# ecu1.net
KiCad netlist of a schematic drawn in EAGLE
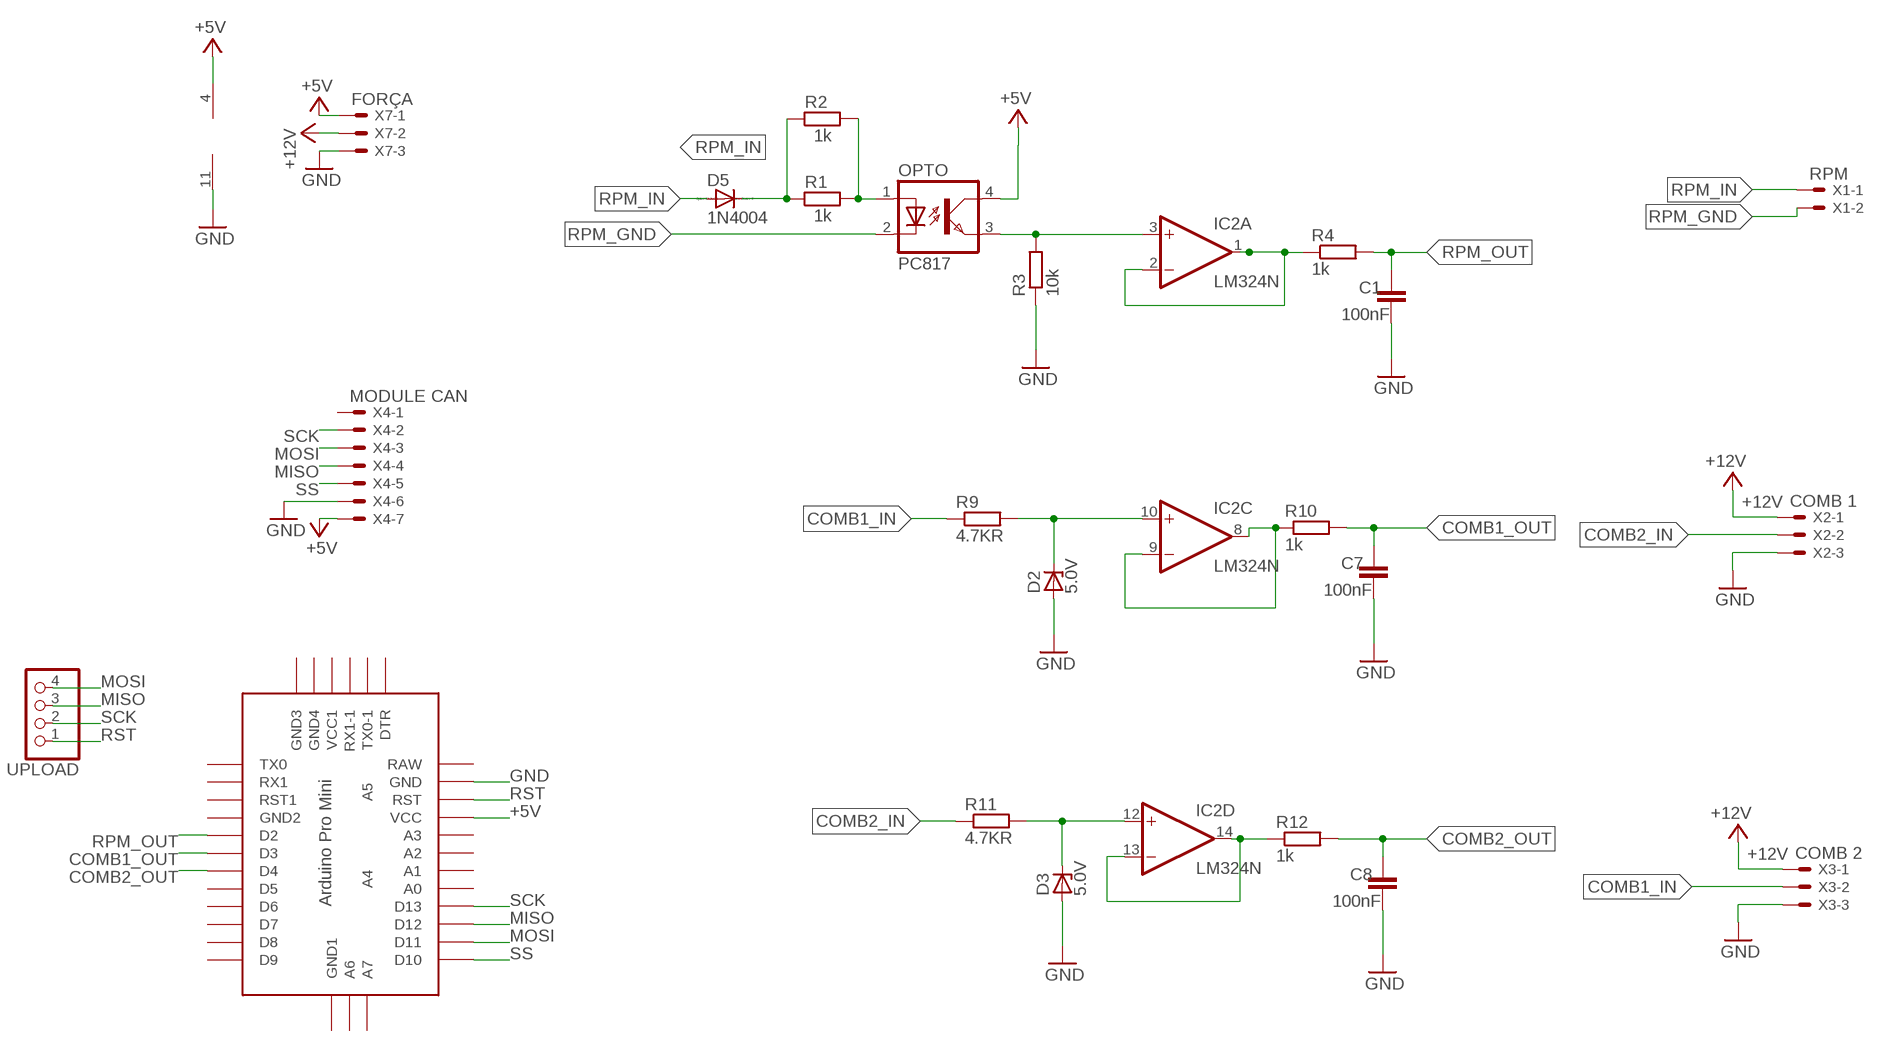
[diagram p0: schematic, sheet 1]

(export (version "E")
  (design (tool "Eeschema 10.0.6"))
  (components
    (comp (ref "C1")
      (value "100nF")
      (footprint "eagle-import:C5B2.5")
      (libsource (lib "eagle-import") (part "C5/2.5"))
    )
    (comp (ref "C7")
      (value "100nF")
      (footprint "eagle-import:C5B2.5")
      (libsource (lib "eagle-import") (part "C5/2.5"))
    )
    (comp (ref "C8")
      (value "100nF")
      (footprint "eagle-import:C5B2.5")
      (libsource (lib "eagle-import") (part "C5/2.5"))
    )
    (comp (ref "D2")
      (value "5.0V")
      (footprint "eagle-import:DO34Z7")
      (libsource (lib "eagle-import") (part "ZENER-DIODEDO34-7"))
    )
    (comp (ref "D3")
      (value "5.0V")
      (footprint "eagle-import:DO34Z7")
      (libsource (lib "eagle-import") (part "ZENER-DIODEDO34-7"))
    )
    (comp (ref "D5")
      (value "1N4004")
      (footprint "eagle-import:DO41-10")
      (libsource (lib "eagle-import") (part "1N4004"))
    )
    (comp (ref "IC2")
      (value "LM324N")
      (footprint "eagle-import:DIL14")
      (libsource (lib "eagle-import") (part "LM324N"))
    )
    (comp (ref "OPTO")
      (value "PC817")
      (footprint "eagle-import:DIL04")
      (fields (field (name "MPN") "PC817X4J000F"))
      (libsource (lib "eagle-import") (part "PC817"))
    )
    (comp (ref "R1")
      (value "1k")
      (footprint "eagle-import:0207_7")
      (libsource (lib "eagle-import") (part "R-EU_0207/7"))
    )
    (comp (ref "R2")
      (value "1k")
      (footprint "eagle-import:0207_7")
      (libsource (lib "eagle-import") (part "R-EU_0207/7"))
    )
    (comp (ref "R3")
      (value "10k")
      (footprint "eagle-import:0207_7")
      (libsource (lib "eagle-import") (part "R-EU_0207/7"))
    )
    (comp (ref "R4")
      (value "1k")
      (footprint "eagle-import:0207_7")
      (libsource (lib "eagle-import") (part "R-EU_0207/7"))
    )
    (comp (ref "R9")
      (value "4.7KR")
      (footprint "eagle-import:0207_7")
      (libsource (lib "eagle-import") (part "R-EU_0207/7"))
    )
    (comp (ref "R10")
      (value "1k")
      (footprint "eagle-import:0207_7")
      (libsource (lib "eagle-import") (part "R-EU_0207/7"))
    )
    (comp (ref "R11")
      (value "4.7KR")
      (footprint "eagle-import:0207_7")
      (libsource (lib "eagle-import") (part "R-EU_0207/7"))
    )
    (comp (ref "R12")
      (value "1k")
      (footprint "eagle-import:0207_7")
      (libsource (lib "eagle-import") (part "R-EU_0207/7"))
    )
    (comp (ref "U$1")
      (value "ABK-PRO-MINI")
      (footprint "eagle-import:ABK-PRO-MINI")
      (libsource (lib "eagle-import") (part "ABK-PRO-MINI"))
    )
    (comp (ref "UPLOAD")
      (value "PINHD-1X4")
      (footprint "eagle-import:1X04")
      (libsource (lib "eagle-import") (part "PINHD-1X4"))
    )
    (comp (ref "X1")
      (value "RPM")
      (footprint "eagle-import:22-23-2021")
      (fields (field (name "MF") "MOLEX") (field (name "MPN") "22-23-2021"))
      (libsource (lib "eagle-import") (part "22-23-2021"))
    )
    (comp (ref "X2")
      (value "COMB 1")
      (footprint "eagle-import:22-23-2031")
      (fields (field (name "MF") "MOLEX") (field (name "MPN") "22-23-2031"))
      (libsource (lib "eagle-import") (part "22-23-2031"))
    )
    (comp (ref "X3")
      (value "COMB 2")
      (footprint "eagle-import:22-23-2031")
      (fields (field (name "MF") "MOLEX") (field (name "MPN") "22-23-2031"))
      (libsource (lib "eagle-import") (part "22-23-2031"))
    )
    (comp (ref "X4")
      (value "MODULE CAN")
      (footprint "eagle-import:22-23-2071")
      (fields (field (name "MF") "MOLEX") (field (name "MPN") "22-23-2071"))
      (libsource (lib "eagle-import") (part "22-23-2071"))
    )
    (comp (ref "X7")
      (value "FORÇA")
      (footprint "eagle-import:22-23-2031")
      (fields (field (name "MF") "MOLEX") (field (name "MPN") "22-23-2031"))
      (libsource (lib "eagle-import") (part "22-23-2031"))
    )
  )
  (nets
    (net (code "1") (name "+5V") (class "Default")
      (node (ref "IC2") (pin "4") (pinfunction "V+_4") (pintype "power_in"))
      (node (ref "OPTO") (pin "4") (pinfunction "COL_4") (pintype "passive"))
      (node (ref "U$1") (pin "VCC") (pinfunction "VCC_VCC") (pintype "bidirectional"))
      (node (ref "X4") (pin "7") (pinfunction "S_7") (pintype "passive"))
      (node (ref "X7") (pin "1") (pinfunction "S_1") (pintype "passive"))
    )
    (net (code "2") (name "+12V") (class "Default")
      (node (ref "X2") (pin "1") (pinfunction "S_1") (pintype "passive"))
      (node (ref "X3") (pin "1") (pinfunction "S_1") (pintype "passive"))
      (node (ref "X7") (pin "2") (pinfunction "S_2") (pintype "passive"))
    )
    (net (code "3") (name "/MISO") (class "Default")
      (node (ref "U$1") (pin "D12") (pinfunction "D12_D12") (pintype "bidirectional"))
      (node (ref "UPLOAD") (pin "3") (pinfunction "3_3") (pintype "passive"))
      (node (ref "X4") (pin "4") (pinfunction "S_4") (pintype "passive"))
    )
    (net (code "4") (name "/MOSI") (class "Default")
      (node (ref "U$1") (pin "D11") (pinfunction "D11_D11") (pintype "bidirectional"))
      (node (ref "UPLOAD") (pin "4") (pinfunction "4_4") (pintype "passive"))
      (node (ref "X4") (pin "3") (pinfunction "S_3") (pintype "passive"))
    )
    (net (code "5") (name "/RST") (class "Default")
      (node (ref "U$1") (pin "RST") (pinfunction "RST_RST") (pintype "bidirectional"))
      (node (ref "UPLOAD") (pin "1") (pinfunction "1_1") (pintype "passive"))
    )
    (net (code "6") (name "/SCK") (class "Default")
      (node (ref "U$1") (pin "D13") (pinfunction "D13_D13") (pintype "bidirectional"))
      (node (ref "UPLOAD") (pin "2") (pinfunction "2_2") (pintype "passive"))
      (node (ref "X4") (pin "2") (pinfunction "S_2") (pintype "passive"))
    )
    (net (code "7") (name "/SS") (class "Default")
      (node (ref "U$1") (pin "D10") (pinfunction "D10_D10") (pintype "bidirectional"))
      (node (ref "X4") (pin "5") (pinfunction "S_5") (pintype "passive"))
    )
    (net (code "8") (name "COMB1_IN") (class "Default")
      (node (ref "R9") (pin "1") (pinfunction "1_1") (pintype "passive"))
      (node (ref "X3") (pin "2") (pinfunction "S_2") (pintype "passive"))
    )
    (net (code "9") (name "COMB1_OUT") (class "Default")
      (node (ref "C7") (pin "2") (pinfunction "2_2") (pintype "passive"))
      (node (ref "R10") (pin "2") (pinfunction "2_2") (pintype "passive"))
      (node (ref "U$1") (pin "D3") (pinfunction "D3_D3") (pintype "bidirectional"))
    )
    (net (code "10") (name "COMB2_IN") (class "Default")
      (node (ref "R11") (pin "1") (pinfunction "1_1") (pintype "passive"))
      (node (ref "X2") (pin "2") (pinfunction "S_2") (pintype "passive"))
    )
    (net (code "11") (name "COMB2_OUT") (class "Default")
      (node (ref "C8") (pin "2") (pinfunction "2_2") (pintype "passive"))
      (node (ref "R12") (pin "2") (pinfunction "2_2") (pintype "passive"))
      (node (ref "U$1") (pin "D4") (pinfunction "D4_D4") (pintype "bidirectional"))
    )
    (net (code "12") (name "GND") (class "Default")
      (node (ref "C1") (pin "1") (pinfunction "1_1") (pintype "passive"))
      (node (ref "C7") (pin "1") (pinfunction "1_1") (pintype "passive"))
      (node (ref "C8") (pin "1") (pinfunction "1_1") (pintype "passive"))
      (node (ref "D2") (pin "A") (pinfunction "A_A") (pintype "passive"))
      (node (ref "D3") (pin "A") (pinfunction "A_A") (pintype "passive"))
      (node (ref "IC2") (pin "11") (pinfunction "V-_11") (pintype "power_in"))
      (node (ref "R3") (pin "1") (pinfunction "1_1") (pintype "passive"))
      (node (ref "U$1") (pin "GND") (pinfunction "GND_GND") (pintype "bidirectional"))
      (node (ref "X2") (pin "3") (pinfunction "S_3") (pintype "passive"))
      (node (ref "X3") (pin "3") (pinfunction "S_3") (pintype "passive"))
      (node (ref "X4") (pin "6") (pinfunction "S_6") (pintype "passive"))
      (node (ref "X7") (pin "3") (pinfunction "S_3") (pintype "passive"))
    )
    (net (code "13") (name "Net-(D5-PadC)") (class "Default")
      (node (ref "D5") (pin "C") (pinfunction "C_C") (pintype "passive"))
      (node (ref "R1") (pin "1") (pinfunction "1_1") (pintype "passive"))
      (node (ref "R2") (pin "1") (pinfunction "1_1") (pintype "passive"))
    )
    (net (code "14") (name "Net-(IC2A-+IN)") (class "Default")
      (node (ref "IC2") (pin "3") (pinfunction "+IN_3") (pintype "input"))
      (node (ref "OPTO") (pin "3") (pinfunction "EMIT_3") (pintype "passive"))
      (node (ref "R3") (pin "2") (pinfunction "2_2") (pintype "passive"))
    )
    (net (code "15") (name "Net-(IC2A--IN)") (class "Default")
      (node (ref "IC2") (pin "1") (pinfunction "OUT_1") (pintype "output"))
      (node (ref "IC2") (pin "2") (pinfunction "-IN_2") (pintype "input"))
      (node (ref "R4") (pin "1") (pinfunction "1_1") (pintype "passive"))
    )
    (net (code "16") (name "Net-(IC2C-+IN)") (class "Default")
      (node (ref "D2") (pin "C") (pinfunction "C_C") (pintype "passive"))
      (node (ref "IC2") (pin "10") (pinfunction "+IN_10") (pintype "input"))
      (node (ref "R9") (pin "2") (pinfunction "2_2") (pintype "passive"))
    )
    (net (code "17") (name "Net-(IC2C--IN)") (class "Default")
      (node (ref "IC2") (pin "8") (pinfunction "OUT_8") (pintype "output"))
      (node (ref "IC2") (pin "9") (pinfunction "-IN_9") (pintype "input"))
      (node (ref "R10") (pin "1") (pinfunction "1_1") (pintype "passive"))
    )
    (net (code "18") (name "Net-(IC2D-+IN)") (class "Default")
      (node (ref "D3") (pin "C") (pinfunction "C_C") (pintype "passive"))
      (node (ref "IC2") (pin "12") (pinfunction "+IN_12") (pintype "input"))
      (node (ref "R11") (pin "2") (pinfunction "2_2") (pintype "passive"))
    )
    (net (code "19") (name "Net-(IC2D--IN)") (class "Default")
      (node (ref "IC2") (pin "13") (pinfunction "-IN_13") (pintype "input"))
      (node (ref "IC2") (pin "14") (pinfunction "OUT_14") (pintype "output"))
      (node (ref "R12") (pin "1") (pinfunction "1_1") (pintype "passive"))
    )
    (net (code "20") (name "Net-(OPTO-A)") (class "Default")
      (node (ref "OPTO") (pin "1") (pinfunction "A_1") (pintype "passive"))
      (node (ref "R1") (pin "2") (pinfunction "2_2") (pintype "passive"))
      (node (ref "R2") (pin "2") (pinfunction "2_2") (pintype "passive"))
    )
    (net (code "21") (name "RPM_GND") (class "Default")
      (node (ref "OPTO") (pin "2") (pinfunction "C_2") (pintype "passive"))
      (node (ref "X1") (pin "2") (pinfunction "S_2") (pintype "passive"))
    )
    (net (code "22") (name "RPM_IN") (class "Default")
      (node (ref "D5") (pin "A") (pinfunction "A_A") (pintype "passive"))
      (node (ref "X1") (pin "1") (pinfunction "S_1") (pintype "passive"))
    )
    (net (code "23") (name "RPM_OUT") (class "Default")
      (node (ref "C1") (pin "2") (pinfunction "2_2") (pintype "passive"))
      (node (ref "R4") (pin "2") (pinfunction "2_2") (pintype "passive"))
      (node (ref "U$1") (pin "D2") (pinfunction "D2_D2") (pintype "bidirectional"))
    )
    (net (code "24") (name "unconnected-(U$1-GND1-PadGND4)") (class "Default")
      (node (ref "U$1") (pin "GND4") (pinfunction "GND1_GND4") (pintype "bidirectional"))
    )
    (net (code "25") (name "unconnected-(U$1-GND2-PadGND1)") (class "Default")
      (node (ref "U$1") (pin "GND1") (pinfunction "GND2_GND1") (pintype "bidirectional"))
    )
    (net (code "26") (name "unconnected-(U$1-GND3-PadGND2)") (class "Default")
      (node (ref "U$1") (pin "GND2") (pinfunction "GND3_GND2") (pintype "bidirectional"))
    )
    (net (code "27") (name "unconnected-(U$1-GND4-PadGND3)") (class "Default")
      (node (ref "U$1") (pin "GND3") (pinfunction "GND4_GND3") (pintype "bidirectional"))
    )
    (net (code "28") (name "unconnected-(U$1-PadA0)") (class "Default")
      (node (ref "U$1") (pin "A0") (pinfunction "A0_A0") (pintype "bidirectional"))
    )
    (net (code "29") (name "unconnected-(U$1-PadA1)") (class "Default")
      (node (ref "U$1") (pin "A1") (pinfunction "A1_A1") (pintype "bidirectional"))
    )
    (net (code "30") (name "unconnected-(U$1-PadA2)") (class "Default")
      (node (ref "U$1") (pin "A2") (pinfunction "A2_A2") (pintype "bidirectional"))
    )
    (net (code "31") (name "unconnected-(U$1-PadA3)") (class "Default")
      (node (ref "U$1") (pin "A3") (pinfunction "A3_A3") (pintype "bidirectional"))
    )
    (net (code "32") (name "unconnected-(U$1-PadA4)") (class "Default")
      (node (ref "U$1") (pin "A4") (pinfunction "A4_A4") (pintype "bidirectional"))
    )
    (net (code "33") (name "unconnected-(U$1-PadA5)") (class "Default")
      (node (ref "U$1") (pin "A5") (pinfunction "A5_A5") (pintype "bidirectional"))
    )
    (net (code "34") (name "unconnected-(U$1-PadA6)") (class "Default")
      (node (ref "U$1") (pin "A6") (pinfunction "A6_A6") (pintype "bidirectional"))
    )
    (net (code "35") (name "unconnected-(U$1-PadA7)") (class "Default")
      (node (ref "U$1") (pin "A7") (pinfunction "A7_A7") (pintype "bidirectional"))
    )
    (net (code "36") (name "unconnected-(U$1-PadD5)") (class "Default")
      (node (ref "U$1") (pin "D5") (pinfunction "D5_D5") (pintype "bidirectional"))
    )
    (net (code "37") (name "unconnected-(U$1-PadD6)") (class "Default")
      (node (ref "U$1") (pin "D6") (pinfunction "D6_D6") (pintype "bidirectional"))
    )
    (net (code "38") (name "unconnected-(U$1-PadD7)") (class "Default")
      (node (ref "U$1") (pin "D7") (pinfunction "D7_D7") (pintype "bidirectional"))
    )
    (net (code "39") (name "unconnected-(U$1-PadD8)") (class "Default")
      (node (ref "U$1") (pin "D8") (pinfunction "D8_D8") (pintype "bidirectional"))
    )
    (net (code "40") (name "unconnected-(U$1-PadD9)") (class "Default")
      (node (ref "U$1") (pin "D9") (pinfunction "D9_D9") (pintype "bidirectional"))
    )
    (net (code "41") (name "unconnected-(U$1-PadDTR)") (class "Default")
      (node (ref "U$1") (pin "DTR") (pinfunction "DTR_DTR") (pintype "bidirectional"))
    )
    (net (code "42") (name "unconnected-(U$1-PadRAW)") (class "Default")
      (node (ref "U$1") (pin "RAW") (pinfunction "RAW_RAW") (pintype "bidirectional"))
    )
    (net (code "43") (name "unconnected-(U$1-PadRST1)") (class "Default")
      (node (ref "U$1") (pin "RST1") (pinfunction "RST1_RST1") (pintype "bidirectional"))
    )
    (net (code "44") (name "unconnected-(U$1-PadRX1)") (class "Default")
      (node (ref "U$1") (pin "RX1") (pinfunction "RX1_RX1") (pintype "bidirectional"))
    )
    (net (code "45") (name "unconnected-(U$1-PadRX1-1)") (class "Default")
      (node (ref "U$1") (pin "RX1-1") (pinfunction "RX1-1_RX1-1") (pintype "bidirectional"))
    )
    (net (code "46") (name "unconnected-(U$1-PadTX0)") (class "Default")
      (node (ref "U$1") (pin "TX0") (pinfunction "TX0_TX0") (pintype "bidirectional"))
    )
    (net (code "47") (name "unconnected-(U$1-PadTX0-1)") (class "Default")
      (node (ref "U$1") (pin "TX0-1") (pinfunction "TX0-1_TX0-1") (pintype "bidirectional"))
    )
    (net (code "48") (name "unconnected-(U$1-PadVCC1)") (class "Default")
      (node (ref "U$1") (pin "VCC1") (pinfunction "VCC1_VCC1") (pintype "bidirectional"))
    )
    (net (code "49") (name "unconnected-(X4A-S-Pad1)") (class "Default")
      (node (ref "X4") (pin "1") (pinfunction "S_1") (pintype "passive"))
    )
  )
)
